# Fake6509_v3.net
KiCad netlist of a schematic drawn in EAGLE
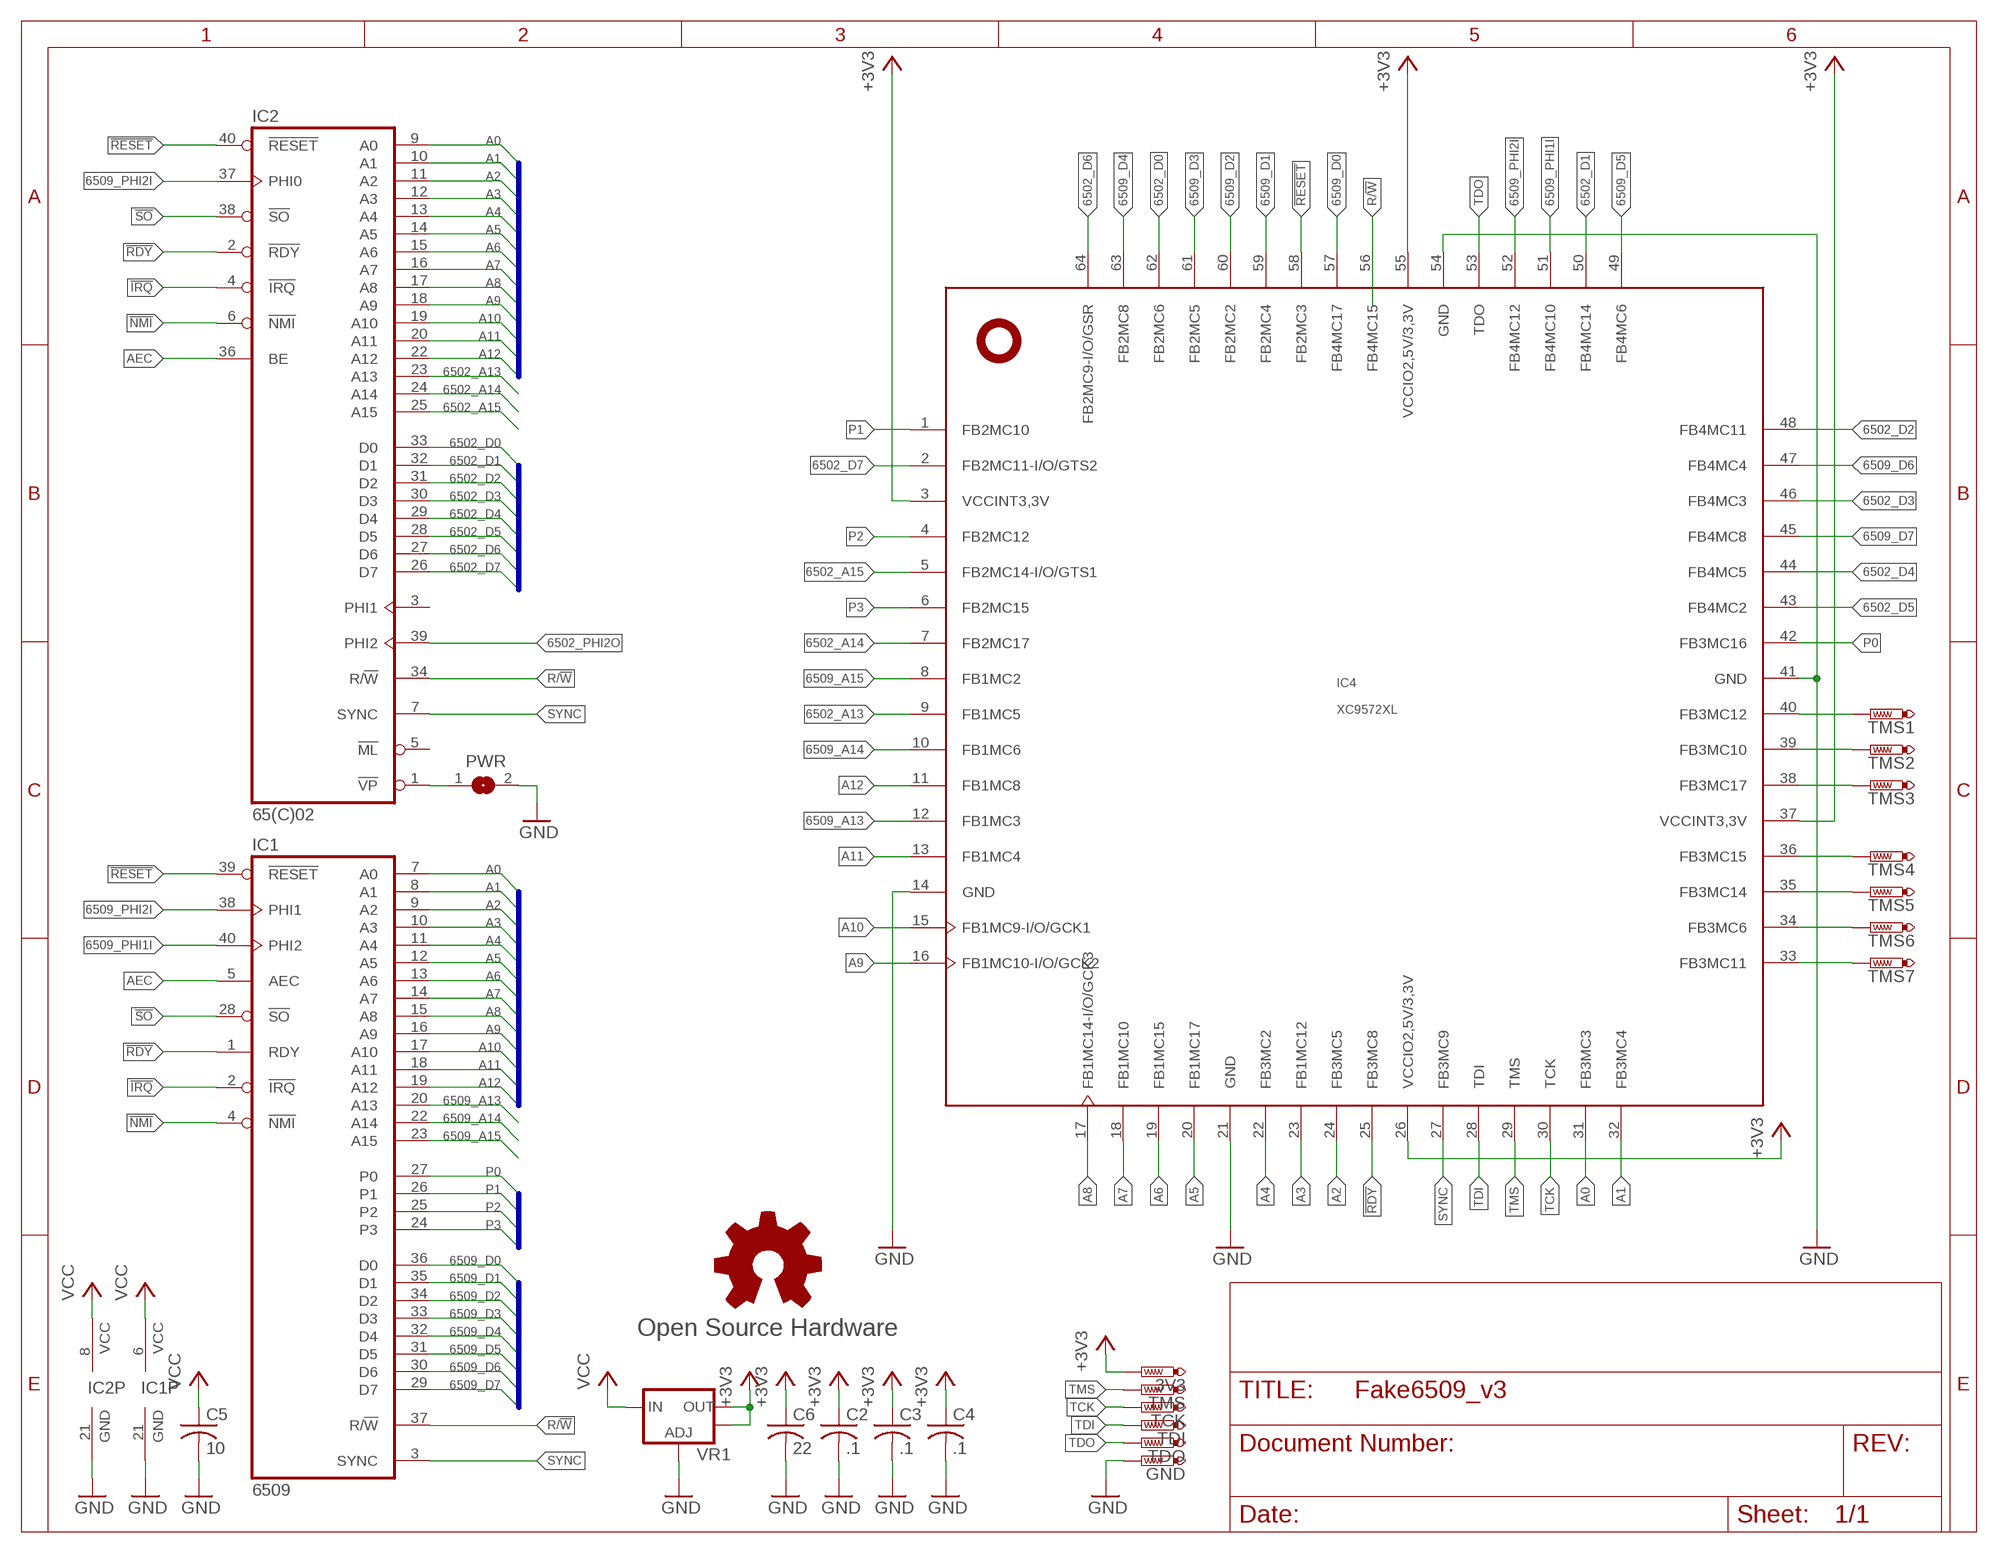
[diagram p0: schematic, sheet 1]

(export (version "E")
  (design (tool "Eeschema 10.0.6"))
  (components
    (comp (ref "3V3")
      (value "PTR1TP08R")
      (footprint "eagle-import:TP08R")
      (libsource (lib "eagle-import") (part "PTR1TP08R"))
    )
    (comp (ref "C2")
      (value ".1")
      (footprint "eagle-import:C0402")
      (libsource (lib "eagle-import") (part "C-USC0402"))
    )
    (comp (ref "C3")
      (value ".1")
      (footprint "eagle-import:C0402")
      (libsource (lib "eagle-import") (part "C-USC0402"))
    )
    (comp (ref "C4")
      (value ".1")
      (footprint "eagle-import:C0402")
      (libsource (lib "eagle-import") (part "C-USC0402"))
    )
    (comp (ref "C5")
      (value "10")
      (footprint "eagle-import:C0805")
      (libsource (lib "eagle-import") (part "C-USC0805"))
    )
    (comp (ref "C6")
      (value "22")
      (footprint "eagle-import:C0805")
      (libsource (lib "eagle-import") (part "C-USC0805"))
    )
    (comp (ref "GND")
      (value "PTR1TP08R")
      (footprint "eagle-import:TP08R")
      (libsource (lib "eagle-import") (part "PTR1TP08R"))
    )
    (comp (ref "GOLD_ORB_SM1")
      (value "Open Source Hardware")
      (footprint "eagle-import:OSHW_5MM")
      (libsource (lib "eagle-import") (part "OSHWLOGOLOGO5MM"))
    )
    (comp (ref "IC1")
      (value "6509")
      (footprint "eagle-import:DIL40-ROUNDPAD")
      (libsource (lib "eagle-import") (part "6509-RP"))
    )
    (comp (ref "IC2")
      (value "65(C)02")
      (footprint "eagle-import:DIL40-ROUNDPAD")
      (libsource (lib "eagle-import") (part "W65C02SP-R"))
    )
    (comp (ref "IC4")
      (value "XC9572XL")
      (footprint "eagle-import:VQFP64")
      (libsource (lib "eagle-import") (part "XC9572XLVQG64"))
    )
    (comp (ref "PWR") (value "SJ") (footprint "eagle-import:SJ") (libsource (lib "eagle-import") (part "SJ")))
    (comp (ref "TCK")
      (value "PTR1TP08R")
      (footprint "eagle-import:TP08R")
      (libsource (lib "eagle-import") (part "PTR1TP08R"))
    )
    (comp (ref "TDI")
      (value "PTR1TP08R")
      (footprint "eagle-import:TP08R")
      (libsource (lib "eagle-import") (part "PTR1TP08R"))
    )
    (comp (ref "TDO")
      (value "PTR1TP08R")
      (footprint "eagle-import:TP08R")
      (libsource (lib "eagle-import") (part "PTR1TP08R"))
    )
    (comp (ref "TMS")
      (value "PTR1TP08R")
      (footprint "eagle-import:TP08R")
      (libsource (lib "eagle-import") (part "PTR1TP08R"))
    )
    (comp (ref "TMS1")
      (value "PTR1TP08R")
      (footprint "eagle-import:TP08R")
      (libsource (lib "eagle-import") (part "PTR1TP08R"))
    )
    (comp (ref "TMS2")
      (value "PTR1TP08R")
      (footprint "eagle-import:TP08R")
      (libsource (lib "eagle-import") (part "PTR1TP08R"))
    )
    (comp (ref "TMS3")
      (value "PTR1TP08R")
      (footprint "eagle-import:TP08R")
      (libsource (lib "eagle-import") (part "PTR1TP08R"))
    )
    (comp (ref "TMS4")
      (value "PTR1TP08R")
      (footprint "eagle-import:TP08R")
      (libsource (lib "eagle-import") (part "PTR1TP08R"))
    )
    (comp (ref "TMS5")
      (value "PTR1TP08R")
      (footprint "eagle-import:TP08R")
      (libsource (lib "eagle-import") (part "PTR1TP08R"))
    )
    (comp (ref "TMS6")
      (value "PTR1TP08R")
      (footprint "eagle-import:TP08R")
      (libsource (lib "eagle-import") (part "PTR1TP08R"))
    )
    (comp (ref "TMS7")
      (value "PTR1TP08R")
      (footprint "eagle-import:TP08R")
      (libsource (lib "eagle-import") (part "PTR1TP08R"))
    )
    (comp (ref "VR1")
      (value "V_REG_LM1117SOT223")
      (footprint "eagle-import:SOT223")
      (libsource (lib "eagle-import") (part "V_REG_LM1117SOT223"))
    )
  )
  (nets
    (net (code "1") (name "+3V3") (class "Default")
      (node (ref "3V3") (pin "TP") (pinfunction "TP_TP") (pintype "input"))
      (node (ref "C2") (pin "1") (pinfunction "1_1") (pintype "passive"))
      (node (ref "C3") (pin "1") (pinfunction "1_1") (pintype "passive"))
      (node (ref "C4") (pin "1") (pinfunction "1_1") (pintype "passive"))
      (node (ref "C6") (pin "1") (pinfunction "1_1") (pintype "passive"))
      (node (ref "IC4") (pin "26") (pinfunction "VCCIO2,5V/3,3V_26") (pintype "power_in"))
      (node (ref "IC4") (pin "3") (pinfunction "VCCINT3,3V_3") (pintype "power_in"))
      (node (ref "IC4") (pin "37") (pinfunction "VCCINT3,3V_37") (pintype "power_in"))
      (node (ref "IC4") (pin "55") (pinfunction "VCCIO2,5V/3,3V_55") (pintype "power_in"))
      (node (ref "VR1") (pin "2") (pinfunction "OUT_2") (pintype "output"))
      (node (ref "VR1") (pin "4") (pinfunction "OUT_4") (pintype "output"))
    )
    (net (code "2") (name "/R{slash}~{W}") (class "Default")
      (node (ref "IC1") (pin "37") (pinfunction "R/~{W}_37") (pintype "output"))
      (node (ref "IC2") (pin "34") (pinfunction "R/~{W}_34") (pintype "output"))
      (node (ref "IC4") (pin "56") (pinfunction "FB4MC15_56") (pintype "bidirectional"))
    )
    (net (code "3") (name "/~{IRQ}") (class "Default")
      (node (ref "IC1") (pin "2") (pinfunction "~{IRQ}_2") (pintype "input"))
      (node (ref "IC2") (pin "4") (pinfunction "~{IRQ}_4") (pintype "input"))
    )
    (net (code "4") (name "/~{NMI}") (class "Default")
      (node (ref "IC1") (pin "4") (pinfunction "~{NMI}_4") (pintype "input"))
      (node (ref "IC2") (pin "6") (pinfunction "~{NMI}_6") (pintype "input"))
    )
    (net (code "5") (name "/~{RDY}") (class "Default")
      (node (ref "IC1") (pin "1") (pinfunction "RDY_1") (pintype "input"))
      (node (ref "IC2") (pin "2") (pinfunction "~{RDY}_2") (pintype "bidirectional"))
      (node (ref "IC4") (pin "25") (pinfunction "FB3MC8_25") (pintype "bidirectional"))
    )
    (net (code "6") (name "/~{RESET}") (class "Default")
      (node (ref "IC1") (pin "39") (pinfunction "~{RESET}_39") (pintype "input"))
      (node (ref "IC2") (pin "40") (pinfunction "~{RESET}_40") (pintype "input"))
      (node (ref "IC4") (pin "58") (pinfunction "FB2MC3_58") (pintype "bidirectional"))
    )
    (net (code "7") (name "/~{SO}") (class "Default")
      (node (ref "IC1") (pin "28") (pinfunction "~{SO}_28") (pintype "input"))
      (node (ref "IC2") (pin "38") (pinfunction "~{SO}_38") (pintype "input"))
    )
    (net (code "8") (name "6502_A13") (class "Default")
      (node (ref "IC2") (pin "23") (pinfunction "A13_23") (pintype "bidirectional"))
      (node (ref "IC4") (pin "9") (pinfunction "FB1MC5_9") (pintype "bidirectional"))
    )
    (net (code "9") (name "6502_A14") (class "Default")
      (node (ref "IC2") (pin "24") (pinfunction "A14_24") (pintype "bidirectional"))
      (node (ref "IC4") (pin "7") (pinfunction "FB2MC17_7") (pintype "bidirectional"))
    )
    (net (code "10") (name "6502_A15") (class "Default")
      (node (ref "IC2") (pin "25") (pinfunction "A15_25") (pintype "bidirectional"))
      (node (ref "IC4") (pin "5") (pinfunction "FB2MC14-I/O/GTS1_5") (pintype "bidirectional"))
    )
    (net (code "11") (name "6502_D0") (class "Default")
      (node (ref "IC2") (pin "33") (pinfunction "D0_33") (pintype "bidirectional"))
      (node (ref "IC4") (pin "62") (pinfunction "FB2MC6_62") (pintype "bidirectional"))
    )
    (net (code "12") (name "6502_D1") (class "Default")
      (node (ref "IC2") (pin "32") (pinfunction "D1_32") (pintype "bidirectional"))
      (node (ref "IC4") (pin "50") (pinfunction "FB4MC14_50") (pintype "bidirectional"))
    )
    (net (code "13") (name "6502_D2") (class "Default")
      (node (ref "IC2") (pin "31") (pinfunction "D2_31") (pintype "bidirectional"))
      (node (ref "IC4") (pin "48") (pinfunction "FB4MC11_48") (pintype "bidirectional"))
    )
    (net (code "14") (name "6502_D3") (class "Default")
      (node (ref "IC2") (pin "30") (pinfunction "D3_30") (pintype "bidirectional"))
      (node (ref "IC4") (pin "46") (pinfunction "FB4MC3_46") (pintype "bidirectional"))
    )
    (net (code "15") (name "6502_D4") (class "Default")
      (node (ref "IC2") (pin "29") (pinfunction "D4_29") (pintype "bidirectional"))
      (node (ref "IC4") (pin "44") (pinfunction "FB4MC5_44") (pintype "bidirectional"))
    )
    (net (code "16") (name "6502_D5") (class "Default")
      (node (ref "IC2") (pin "28") (pinfunction "D5_28") (pintype "bidirectional"))
      (node (ref "IC4") (pin "43") (pinfunction "FB4MC2_43") (pintype "bidirectional"))
    )
    (net (code "17") (name "6502_D6") (class "Default")
      (node (ref "IC2") (pin "27") (pinfunction "D6_27") (pintype "bidirectional"))
      (node (ref "IC4") (pin "64") (pinfunction "FB2MC9-I/O/GSR_64") (pintype "bidirectional"))
    )
    (net (code "18") (name "6502_D7") (class "Default")
      (node (ref "IC2") (pin "26") (pinfunction "D7_26") (pintype "bidirectional"))
      (node (ref "IC4") (pin "2") (pinfunction "FB2MC11-I/O/GTS2_2") (pintype "bidirectional"))
    )
    (net (code "19") (name "6502_PHI2O") (class "Default")
      (node (ref "IC2") (pin "39") (pinfunction "PHI2_39") (pintype "output"))
    )
    (net (code "20") (name "6509_A13") (class "Default")
      (node (ref "IC1") (pin "20") (pinfunction "A13_20") (pintype "output"))
      (node (ref "IC4") (pin "12") (pinfunction "FB1MC3_12") (pintype "bidirectional"))
    )
    (net (code "21") (name "6509_A14") (class "Default")
      (node (ref "IC1") (pin "22") (pinfunction "A14_22") (pintype "output"))
      (node (ref "IC4") (pin "10") (pinfunction "FB1MC6_10") (pintype "bidirectional"))
    )
    (net (code "22") (name "6509_A15") (class "Default")
      (node (ref "IC1") (pin "23") (pinfunction "A15_23") (pintype "output"))
      (node (ref "IC4") (pin "8") (pinfunction "FB1MC2_8") (pintype "bidirectional"))
    )
    (net (code "23") (name "6509_D0") (class "Default")
      (node (ref "IC1") (pin "36") (pinfunction "D0_36") (pintype "bidirectional"))
      (node (ref "IC4") (pin "57") (pinfunction "FB4MC17_57") (pintype "bidirectional"))
    )
    (net (code "24") (name "6509_D1") (class "Default")
      (node (ref "IC1") (pin "35") (pinfunction "D1_35") (pintype "bidirectional"))
      (node (ref "IC4") (pin "59") (pinfunction "FB2MC4_59") (pintype "bidirectional"))
    )
    (net (code "25") (name "6509_D2") (class "Default")
      (node (ref "IC1") (pin "34") (pinfunction "D2_34") (pintype "bidirectional"))
      (node (ref "IC4") (pin "60") (pinfunction "FB2MC2_60") (pintype "bidirectional"))
    )
    (net (code "26") (name "6509_D3") (class "Default")
      (node (ref "IC1") (pin "33") (pinfunction "D3_33") (pintype "bidirectional"))
      (node (ref "IC4") (pin "61") (pinfunction "FB2MC5_61") (pintype "bidirectional"))
    )
    (net (code "27") (name "6509_D4") (class "Default")
      (node (ref "IC1") (pin "32") (pinfunction "D4_32") (pintype "bidirectional"))
      (node (ref "IC4") (pin "63") (pinfunction "FB2MC8_63") (pintype "bidirectional"))
    )
    (net (code "28") (name "6509_D5") (class "Default")
      (node (ref "IC1") (pin "31") (pinfunction "D5_31") (pintype "bidirectional"))
      (node (ref "IC4") (pin "49") (pinfunction "FB4MC6_49") (pintype "bidirectional"))
    )
    (net (code "29") (name "6509_D6") (class "Default")
      (node (ref "IC1") (pin "30") (pinfunction "D6_30") (pintype "bidirectional"))
      (node (ref "IC4") (pin "47") (pinfunction "FB4MC4_47") (pintype "bidirectional"))
    )
    (net (code "30") (name "6509_D7") (class "Default")
      (node (ref "IC1") (pin "29") (pinfunction "D7_29") (pintype "bidirectional"))
      (node (ref "IC4") (pin "45") (pinfunction "FB4MC8_45") (pintype "bidirectional"))
    )
    (net (code "31") (name "6509_PHI1I") (class "Default")
      (node (ref "IC1") (pin "40") (pinfunction "PHI2_40") (pintype "input"))
      (node (ref "IC4") (pin "51") (pinfunction "FB4MC10_51") (pintype "bidirectional"))
    )
    (net (code "32") (name "6509_PHI2I") (class "Default")
      (node (ref "IC1") (pin "38") (pinfunction "PHI1_38") (pintype "input"))
      (node (ref "IC2") (pin "37") (pinfunction "PHI0_37") (pintype "input"))
      (node (ref "IC4") (pin "52") (pinfunction "FB4MC12_52") (pintype "bidirectional"))
    )
    (net (code "33") (name "A0") (class "Default")
      (node (ref "IC1") (pin "7") (pinfunction "A0_7") (pintype "output"))
      (node (ref "IC2") (pin "9") (pinfunction "A0_9") (pintype "bidirectional"))
      (node (ref "IC4") (pin "31") (pinfunction "FB3MC3_31") (pintype "bidirectional"))
    )
    (net (code "34") (name "A1") (class "Default")
      (node (ref "IC1") (pin "8") (pinfunction "A1_8") (pintype "output"))
      (node (ref "IC2") (pin "10") (pinfunction "A1_10") (pintype "bidirectional"))
      (node (ref "IC4") (pin "32") (pinfunction "FB3MC4_32") (pintype "bidirectional"))
    )
    (net (code "35") (name "A2") (class "Default")
      (node (ref "IC1") (pin "9") (pinfunction "A2_9") (pintype "output"))
      (node (ref "IC2") (pin "11") (pinfunction "A2_11") (pintype "bidirectional"))
      (node (ref "IC4") (pin "24") (pinfunction "FB3MC5_24") (pintype "bidirectional"))
    )
    (net (code "36") (name "A3") (class "Default")
      (node (ref "IC1") (pin "10") (pinfunction "A3_10") (pintype "output"))
      (node (ref "IC2") (pin "12") (pinfunction "A3_12") (pintype "bidirectional"))
      (node (ref "IC4") (pin "23") (pinfunction "FB1MC12_23") (pintype "bidirectional"))
    )
    (net (code "37") (name "A4") (class "Default")
      (node (ref "IC1") (pin "11") (pinfunction "A4_11") (pintype "output"))
      (node (ref "IC2") (pin "13") (pinfunction "A4_13") (pintype "bidirectional"))
      (node (ref "IC4") (pin "22") (pinfunction "FB3MC2_22") (pintype "bidirectional"))
    )
    (net (code "38") (name "A5") (class "Default")
      (node (ref "IC1") (pin "12") (pinfunction "A5_12") (pintype "output"))
      (node (ref "IC2") (pin "14") (pinfunction "A5_14") (pintype "bidirectional"))
      (node (ref "IC4") (pin "20") (pinfunction "FB1MC17_20") (pintype "bidirectional"))
    )
    (net (code "39") (name "A6") (class "Default")
      (node (ref "IC1") (pin "13") (pinfunction "A6_13") (pintype "output"))
      (node (ref "IC2") (pin "15") (pinfunction "A6_15") (pintype "bidirectional"))
      (node (ref "IC4") (pin "19") (pinfunction "FB1MC15_19") (pintype "bidirectional"))
    )
    (net (code "40") (name "A7") (class "Default")
      (node (ref "IC1") (pin "14") (pinfunction "A7_14") (pintype "output"))
      (node (ref "IC2") (pin "16") (pinfunction "A7_16") (pintype "bidirectional"))
      (node (ref "IC4") (pin "18") (pinfunction "FB1MC10_18") (pintype "bidirectional"))
    )
    (net (code "41") (name "A8") (class "Default")
      (node (ref "IC1") (pin "15") (pinfunction "A8_15") (pintype "output"))
      (node (ref "IC2") (pin "17") (pinfunction "A8_17") (pintype "bidirectional"))
      (node (ref "IC4") (pin "17") (pinfunction "FB1MC14-I/O/GCK3_17") (pintype "bidirectional"))
    )
    (net (code "42") (name "A9") (class "Default")
      (node (ref "IC1") (pin "16") (pinfunction "A9_16") (pintype "output"))
      (node (ref "IC2") (pin "18") (pinfunction "A9_18") (pintype "bidirectional"))
      (node (ref "IC4") (pin "16") (pinfunction "FB1MC10-I/O/GCK2_16") (pintype "bidirectional"))
    )
    (net (code "43") (name "A10") (class "Default")
      (node (ref "IC1") (pin "17") (pinfunction "A10_17") (pintype "output"))
      (node (ref "IC2") (pin "19") (pinfunction "A10_19") (pintype "bidirectional"))
      (node (ref "IC4") (pin "15") (pinfunction "FB1MC9-I/O/GCK1_15") (pintype "bidirectional"))
    )
    (net (code "44") (name "A11") (class "Default")
      (node (ref "IC1") (pin "18") (pinfunction "A11_18") (pintype "output"))
      (node (ref "IC2") (pin "20") (pinfunction "A11_20") (pintype "bidirectional"))
      (node (ref "IC4") (pin "13") (pinfunction "FB1MC4_13") (pintype "bidirectional"))
    )
    (net (code "45") (name "A12") (class "Default")
      (node (ref "IC1") (pin "19") (pinfunction "A12_19") (pintype "output"))
      (node (ref "IC2") (pin "22") (pinfunction "A12_22") (pintype "bidirectional"))
      (node (ref "IC4") (pin "11") (pinfunction "FB1MC8_11") (pintype "bidirectional"))
    )
    (net (code "46") (name "AEC") (class "Default")
      (node (ref "IC1") (pin "5") (pinfunction "AEC_5") (pintype "input"))
      (node (ref "IC2") (pin "36") (pinfunction "BE_36") (pintype "input"))
    )
    (net (code "47") (name "GND") (class "Default")
      (node (ref "C2") (pin "2") (pinfunction "2_2") (pintype "passive"))
      (node (ref "C3") (pin "2") (pinfunction "2_2") (pintype "passive"))
      (node (ref "C4") (pin "2") (pinfunction "2_2") (pintype "passive"))
      (node (ref "C5") (pin "2") (pinfunction "2_2") (pintype "passive"))
      (node (ref "C6") (pin "2") (pinfunction "2_2") (pintype "passive"))
      (node (ref "GND") (pin "TP") (pinfunction "TP_TP") (pintype "input"))
      (node (ref "IC1") (pin "21") (pinfunction "GND_21") (pintype "power_in"))
      (node (ref "IC2") (pin "21") (pinfunction "GND_21") (pintype "power_in"))
      (node (ref "IC4") (pin "14") (pinfunction "GND_14") (pintype "power_in"))
      (node (ref "IC4") (pin "21") (pinfunction "GND_21") (pintype "power_in"))
      (node (ref "IC4") (pin "41") (pinfunction "GND_41") (pintype "power_in"))
      (node (ref "IC4") (pin "54") (pinfunction "GND_54") (pintype "power_in"))
      (node (ref "PWR") (pin "2") (pinfunction "2_2") (pintype "passive"))
      (node (ref "VR1") (pin "1") (pinfunction "ADJ_1") (pintype "input"))
    )
    (net (code "48") (name "Net-(IC2A-~{VP})") (class "Default")
      (node (ref "IC2") (pin "1") (pinfunction "~{VP}_1") (pintype "output"))
      (node (ref "PWR") (pin "1") (pinfunction "1_1") (pintype "passive"))
    )
    (net (code "49") (name "Net-(IC4-FB3MC6)") (class "Default")
      (node (ref "IC4") (pin "34") (pinfunction "FB3MC6_34") (pintype "bidirectional"))
      (node (ref "TMS6") (pin "TP") (pinfunction "TP_TP") (pintype "input"))
    )
    (net (code "50") (name "Net-(IC4-FB3MC10)") (class "Default")
      (node (ref "IC4") (pin "39") (pinfunction "FB3MC10_39") (pintype "bidirectional"))
      (node (ref "TMS2") (pin "TP") (pinfunction "TP_TP") (pintype "input"))
    )
    (net (code "51") (name "Net-(IC4-FB3MC11)") (class "Default")
      (node (ref "IC4") (pin "33") (pinfunction "FB3MC11_33") (pintype "bidirectional"))
      (node (ref "TMS7") (pin "TP") (pinfunction "TP_TP") (pintype "input"))
    )
    (net (code "52") (name "Net-(IC4-FB3MC12)") (class "Default")
      (node (ref "IC4") (pin "40") (pinfunction "FB3MC12_40") (pintype "bidirectional"))
      (node (ref "TMS1") (pin "TP") (pinfunction "TP_TP") (pintype "input"))
    )
    (net (code "53") (name "Net-(IC4-FB3MC14)") (class "Default")
      (node (ref "IC4") (pin "35") (pinfunction "FB3MC14_35") (pintype "bidirectional"))
      (node (ref "TMS5") (pin "TP") (pinfunction "TP_TP") (pintype "input"))
    )
    (net (code "54") (name "Net-(IC4-FB3MC15)") (class "Default")
      (node (ref "IC4") (pin "36") (pinfunction "FB3MC15_36") (pintype "bidirectional"))
      (node (ref "TMS4") (pin "TP") (pinfunction "TP_TP") (pintype "input"))
    )
    (net (code "55") (name "Net-(IC4-FB3MC17)") (class "Default")
      (node (ref "IC4") (pin "38") (pinfunction "FB3MC17_38") (pintype "bidirectional"))
      (node (ref "TMS3") (pin "TP") (pinfunction "TP_TP") (pintype "input"))
    )
    (net (code "56") (name "P0") (class "Default")
      (node (ref "IC1") (pin "27") (pinfunction "P0_27") (pintype "output"))
      (node (ref "IC4") (pin "42") (pinfunction "FB3MC16_42") (pintype "bidirectional"))
    )
    (net (code "57") (name "P1") (class "Default")
      (node (ref "IC1") (pin "26") (pinfunction "P1_26") (pintype "output"))
      (node (ref "IC4") (pin "1") (pinfunction "FB2MC10_1") (pintype "bidirectional"))
    )
    (net (code "58") (name "P2") (class "Default")
      (node (ref "IC1") (pin "25") (pinfunction "P2_25") (pintype "output"))
      (node (ref "IC4") (pin "4") (pinfunction "FB2MC12_4") (pintype "bidirectional"))
    )
    (net (code "59") (name "P3") (class "Default")
      (node (ref "IC1") (pin "24") (pinfunction "P3_24") (pintype "output"))
      (node (ref "IC4") (pin "6") (pinfunction "FB2MC15_6") (pintype "bidirectional"))
    )
    (net (code "60") (name "SYNC") (class "Default")
      (node (ref "IC1") (pin "3") (pinfunction "SYNC_3") (pintype "output"))
      (node (ref "IC2") (pin "7") (pinfunction "SYNC_7") (pintype "output"))
      (node (ref "IC4") (pin "27") (pinfunction "FB3MC9_27") (pintype "bidirectional"))
    )
    (net (code "61") (name "TCK") (class "Default")
      (node (ref "IC4") (pin "30") (pinfunction "TCK_30") (pintype "bidirectional"))
      (node (ref "TCK") (pin "TP") (pinfunction "TP_TP") (pintype "input"))
    )
    (net (code "62") (name "TDI") (class "Default")
      (node (ref "IC4") (pin "28") (pinfunction "TDI_28") (pintype "bidirectional"))
      (node (ref "TDI") (pin "TP") (pinfunction "TP_TP") (pintype "input"))
    )
    (net (code "63") (name "TDO") (class "Default")
      (node (ref "IC4") (pin "53") (pinfunction "TDO_53") (pintype "bidirectional"))
      (node (ref "TDO") (pin "TP") (pinfunction "TP_TP") (pintype "input"))
    )
    (net (code "64") (name "TMS") (class "Default")
      (node (ref "IC4") (pin "29") (pinfunction "TMS_29") (pintype "bidirectional"))
      (node (ref "TMS") (pin "TP") (pinfunction "TP_TP") (pintype "input"))
    )
    (net (code "65") (name "VCC") (class "Default")
      (node (ref "C5") (pin "1") (pinfunction "1_1") (pintype "passive"))
      (node (ref "IC1") (pin "6") (pinfunction "VCC_6") (pintype "power_in"))
      (node (ref "IC2") (pin "8") (pinfunction "VCC_8") (pintype "power_in"))
      (node (ref "VR1") (pin "3") (pinfunction "IN_3") (pintype "input"))
    )
    (net (code "66") (name "unconnected-(IC2A-PHI1-Pad3)") (class "Default")
      (node (ref "IC2") (pin "3") (pinfunction "PHI1_3") (pintype "output"))
    )
    (net (code "67") (name "unconnected-(IC2A-~{ML}-Pad5)") (class "Default")
      (node (ref "IC2") (pin "5") (pinfunction "~{ML}_5") (pintype "output"))
    )
  )
)
